# RGB_7-segment_breakout.net
KiCad netlist of a schematic drawn in EAGLE
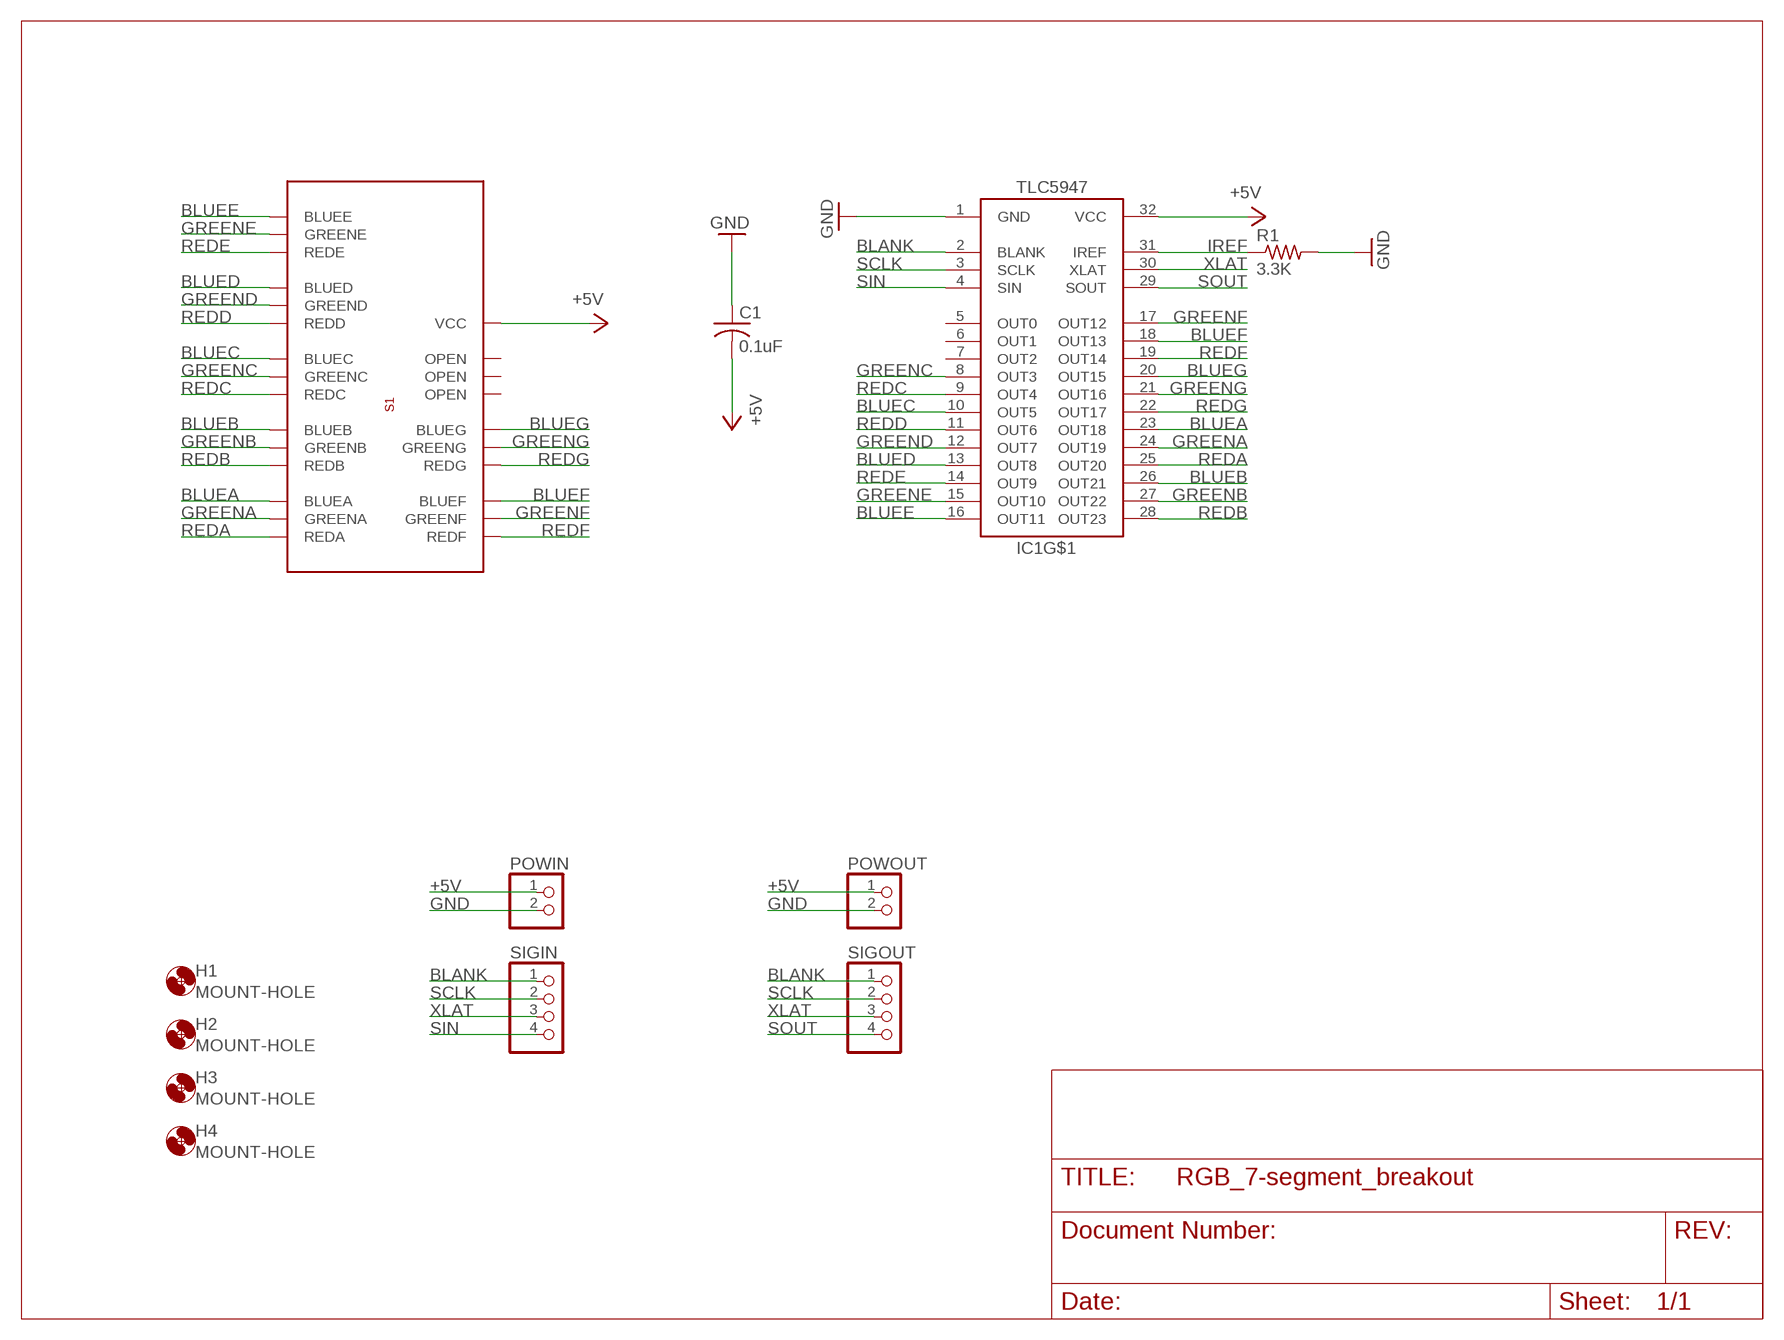
[diagram p0: schematic, sheet 1]

(export (version "E")
  (design (tool "Eeschema 10.0.6"))
  (components
    (comp (ref "C1")
      (value "0.1uF")
      (footprint "eagle-import:C025-025X050")
      (libsource (lib "eagle-import") (part "C-US025-025X050"))
    )
    (comp (ref "H1")
      (value "MOUNT-HOLE")
      (footprint "eagle-import:2,1")
      (libsource (lib "eagle-import") (part "MOUNT-HOLE"))
    )
    (comp (ref "H2")
      (value "MOUNT-HOLE")
      (footprint "eagle-import:2,1")
      (libsource (lib "eagle-import") (part "MOUNT-HOLE"))
    )
    (comp (ref "H3")
      (value "MOUNT-HOLE")
      (footprint "eagle-import:2,1")
      (libsource (lib "eagle-import") (part "MOUNT-HOLE"))
    )
    (comp (ref "H4")
      (value "MOUNT-HOLE")
      (footprint "eagle-import:2,1")
      (libsource (lib "eagle-import") (part "MOUNT-HOLE"))
    )
    (comp (ref "IC1")
      (value "TLC5947-DAP")
      (footprint "eagle-import:HTSSOP32DAP")
      (libsource (lib "eagle-import") (part "TLC5947-DAP"))
    )
    (comp (ref "POWIN")
      (value "PINHD-1X2")
      (footprint "eagle-import:1X02")
      (libsource (lib "eagle-import") (part "PINHD-1X2"))
    )
    (comp (ref "POWOUT")
      (value "PINHD-1X2")
      (footprint "eagle-import:1X02")
      (libsource (lib "eagle-import") (part "PINHD-1X2"))
    )
    (comp (ref "R1")
      (value "3.3K")
      (footprint "eagle-import:0207_10")
      (libsource (lib "eagle-import") (part "R-US_0207/10"))
    )
    (comp (ref "S1")
      (value "AD-121F2")
      (footprint "eagle-import:AD-121F2")
      (libsource (lib "eagle-import") (part "AD-121F2"))
    )
    (comp (ref "SIGIN")
      (value "PINHD-1X4")
      (footprint "eagle-import:1X04")
      (libsource (lib "eagle-import") (part "PINHD-1X4"))
    )
    (comp (ref "SIGOUT")
      (value "PINHD-1X4")
      (footprint "eagle-import:1X04")
      (libsource (lib "eagle-import") (part "PINHD-1X4"))
    )
  )
  (nets
    (net (code "1") (name "+5V") (class "Default")
      (node (ref "C1") (pin "2") (pinfunction "2_2") (pintype "passive"))
      (node (ref "IC1") (pin "32") (pinfunction "VCC_32") (pintype "power_in"))
      (node (ref "POWIN") (pin "1") (pinfunction "1_1") (pintype "passive"))
      (node (ref "POWOUT") (pin "1") (pinfunction "1_1") (pintype "passive"))
      (node (ref "S1") (pin "P$17") (pinfunction "VCC_P$17") (pintype "power_in"))
    )
    (net (code "2") (name "/BLANK") (class "Default")
      (node (ref "IC1") (pin "2") (pinfunction "BLANK_2") (pintype "input"))
      (node (ref "SIGIN") (pin "1") (pinfunction "1_1") (pintype "passive"))
      (node (ref "SIGOUT") (pin "1") (pinfunction "1_1") (pintype "passive"))
    )
    (net (code "3") (name "/BLUEA") (class "Default")
      (node (ref "IC1") (pin "23") (pinfunction "OUT18_23") (pintype "open_collector"))
      (node (ref "S1") (pin "P$21") (pinfunction "BLUEA_P$21") (pintype "open_collector"))
    )
    (net (code "4") (name "/BLUEB") (class "Default")
      (node (ref "IC1") (pin "26") (pinfunction "OUT21_26") (pintype "open_collector"))
      (node (ref "S1") (pin "P$24") (pinfunction "BLUEB_P$24") (pintype "open_collector"))
    )
    (net (code "5") (name "/BLUEC") (class "Default")
      (node (ref "IC1") (pin "10") (pinfunction "OUT5_10") (pintype "open_collector"))
      (node (ref "S1") (pin "P$5") (pinfunction "BLUEC_P$5") (pintype "open_collector"))
    )
    (net (code "6") (name "/BLUED") (class "Default")
      (node (ref "IC1") (pin "13") (pinfunction "OUT8_13") (pintype "open_collector"))
      (node (ref "S1") (pin "P$2") (pinfunction "BLUED_P$2") (pintype "open_collector"))
    )
    (net (code "7") (name "/BLUEE") (class "Default")
      (node (ref "IC1") (pin "16") (pinfunction "OUT11_16") (pintype "open_collector"))
      (node (ref "S1") (pin "P$9") (pinfunction "BLUEE_P$9") (pintype "open_collector"))
    )
    (net (code "8") (name "/BLUEF") (class "Default")
      (node (ref "IC1") (pin "18") (pinfunction "OUT13_18") (pintype "open_collector"))
      (node (ref "S1") (pin "P$18") (pinfunction "BLUEF_P$18") (pintype "open_collector"))
    )
    (net (code "9") (name "/BLUEG") (class "Default")
      (node (ref "IC1") (pin "20") (pinfunction "OUT15_20") (pintype "open_collector"))
      (node (ref "S1") (pin "P$19") (pinfunction "BLUEG_P$19") (pintype "open_collector"))
    )
    (net (code "10") (name "/GREENA") (class "Default")
      (node (ref "IC1") (pin "24") (pinfunction "OUT19_24") (pintype "open_collector"))
      (node (ref "S1") (pin "P$22") (pinfunction "GREENA_P$22") (pintype "open_collector"))
    )
    (net (code "11") (name "/GREENB") (class "Default")
      (node (ref "IC1") (pin "27") (pinfunction "OUT22_27") (pintype "open_collector"))
      (node (ref "S1") (pin "P$16") (pinfunction "GREENB_P$16") (pintype "open_collector"))
    )
    (net (code "12") (name "/GREENC") (class "Default")
      (node (ref "IC1") (pin "8") (pinfunction "OUT3_8") (pintype "open_collector"))
      (node (ref "S1") (pin "P$11") (pinfunction "GREENC_P$11") (pintype "open_collector"))
    )
    (net (code "13") (name "/GREEND") (class "Default")
      (node (ref "IC1") (pin "12") (pinfunction "OUT7_12") (pintype "open_collector"))
      (node (ref "S1") (pin "P$3") (pinfunction "GREEND_P$3") (pintype "open_collector"))
    )
    (net (code "14") (name "/GREENE") (class "Default")
      (node (ref "IC1") (pin "15") (pinfunction "OUT10_15") (pintype "open_collector"))
      (node (ref "S1") (pin "P$1") (pinfunction "GREENE_P$1") (pintype "open_collector"))
    )
    (net (code "15") (name "/GREENF") (class "Default")
      (node (ref "IC1") (pin "17") (pinfunction "OUT12_17") (pintype "open_collector"))
      (node (ref "S1") (pin "P$13") (pinfunction "GREENF_P$13") (pintype "open_collector"))
    )
    (net (code "16") (name "/GREENG") (class "Default")
      (node (ref "IC1") (pin "21") (pinfunction "OUT16_21") (pintype "open_collector"))
      (node (ref "S1") (pin "P$15") (pinfunction "GREENG_P$15") (pintype "open_collector"))
    )
    (net (code "17") (name "/IREF") (class "Default")
      (node (ref "IC1") (pin "31") (pinfunction "IREF_31") (pintype "bidirectional"))
      (node (ref "R1") (pin "1") (pinfunction "1_1") (pintype "passive"))
    )
    (net (code "18") (name "/REDA") (class "Default")
      (node (ref "IC1") (pin "25") (pinfunction "OUT20_25") (pintype "open_collector"))
      (node (ref "S1") (pin "P$23") (pinfunction "REDA_P$23") (pintype "open_collector"))
    )
    (net (code "19") (name "/REDB") (class "Default")
      (node (ref "IC1") (pin "28") (pinfunction "OUT23_28") (pintype "open_collector"))
      (node (ref "S1") (pin "P$25") (pinfunction "REDB_P$25") (pintype "open_collector"))
    )
    (net (code "20") (name "/REDC") (class "Default")
      (node (ref "IC1") (pin "9") (pinfunction "OUT4_9") (pintype "open_collector"))
      (node (ref "S1") (pin "P$6") (pinfunction "REDC_P$6") (pintype "open_collector"))
    )
    (net (code "21") (name "/REDD") (class "Default")
      (node (ref "IC1") (pin "11") (pinfunction "OUT6_11") (pintype "open_collector"))
      (node (ref "S1") (pin "P$4") (pinfunction "REDD_P$4") (pintype "open_collector"))
    )
    (net (code "22") (name "/REDE") (class "Default")
      (node (ref "IC1") (pin "14") (pinfunction "OUT9_14") (pintype "open_collector"))
      (node (ref "S1") (pin "P$10") (pinfunction "REDE_P$10") (pintype "open_collector"))
    )
    (net (code "23") (name "/REDF") (class "Default")
      (node (ref "IC1") (pin "19") (pinfunction "OUT14_19") (pintype "open_collector"))
      (node (ref "S1") (pin "P$14") (pinfunction "REDF_P$14") (pintype "open_collector"))
    )
    (net (code "24") (name "/REDG") (class "Default")
      (node (ref "IC1") (pin "22") (pinfunction "OUT17_22") (pintype "open_collector"))
      (node (ref "S1") (pin "P$20") (pinfunction "REDG_P$20") (pintype "open_collector"))
    )
    (net (code "25") (name "/SCLK") (class "Default")
      (node (ref "IC1") (pin "3") (pinfunction "SCLK_3") (pintype "input"))
      (node (ref "SIGIN") (pin "2") (pinfunction "2_2") (pintype "passive"))
      (node (ref "SIGOUT") (pin "2") (pinfunction "2_2") (pintype "passive"))
    )
    (net (code "26") (name "/SIN") (class "Default")
      (node (ref "IC1") (pin "4") (pinfunction "SIN_4") (pintype "input"))
      (node (ref "SIGIN") (pin "4") (pinfunction "4_4") (pintype "passive"))
    )
    (net (code "27") (name "/SOUT") (class "Default")
      (node (ref "IC1") (pin "29") (pinfunction "SOUT_29") (pintype "output"))
      (node (ref "SIGOUT") (pin "4") (pinfunction "4_4") (pintype "passive"))
    )
    (net (code "28") (name "/XLAT") (class "Default")
      (node (ref "IC1") (pin "30") (pinfunction "XLAT_30") (pintype "input"))
      (node (ref "SIGIN") (pin "3") (pinfunction "3_3") (pintype "passive"))
      (node (ref "SIGOUT") (pin "3") (pinfunction "3_3") (pintype "passive"))
    )
    (net (code "29") (name "GND") (class "Default")
      (node (ref "C1") (pin "1") (pinfunction "1_1") (pintype "passive"))
      (node (ref "IC1") (pin "1") (pinfunction "GND_1") (pintype "power_in"))
      (node (ref "POWIN") (pin "2") (pinfunction "2_2") (pintype "passive"))
      (node (ref "POWOUT") (pin "2") (pinfunction "2_2") (pintype "passive"))
      (node (ref "R1") (pin "2") (pinfunction "2_2") (pintype "passive"))
    )
    (net (code "30") (name "unconnected-(IC1A-OUT0-Pad5)") (class "Default")
      (node (ref "IC1") (pin "5") (pinfunction "OUT0_5") (pintype "open_collector"))
    )
    (net (code "31") (name "unconnected-(IC1A-OUT1-Pad6)") (class "Default")
      (node (ref "IC1") (pin "6") (pinfunction "OUT1_6") (pintype "open_collector"))
    )
    (net (code "32") (name "unconnected-(IC1A-OUT2-Pad7)") (class "Default")
      (node (ref "IC1") (pin "7") (pinfunction "OUT2_7") (pintype "open_collector"))
    )
    (net (code "33") (name "unconnected-(S1-OPEN-PadP$7)") (class "Default")
      (node (ref "S1") (pin "P$7") (pinfunction "OPEN_P$7") (pintype "no_connect"))
    )
    (net (code "34") (name "unconnected-(S1-OPEN-PadP$8)") (class "Default")
      (node (ref "S1") (pin "P$8") (pinfunction "OPEN_P$8") (pintype "no_connect"))
    )
    (net (code "35") (name "unconnected-(S1-OPEN-PadP$12)") (class "Default")
      (node (ref "S1") (pin "P$12") (pinfunction "OPEN_P$12") (pintype "no_connect"))
    )
  )
)
